# 2Rotary.net
KiCad netlist of a schematic drawn in EAGLE
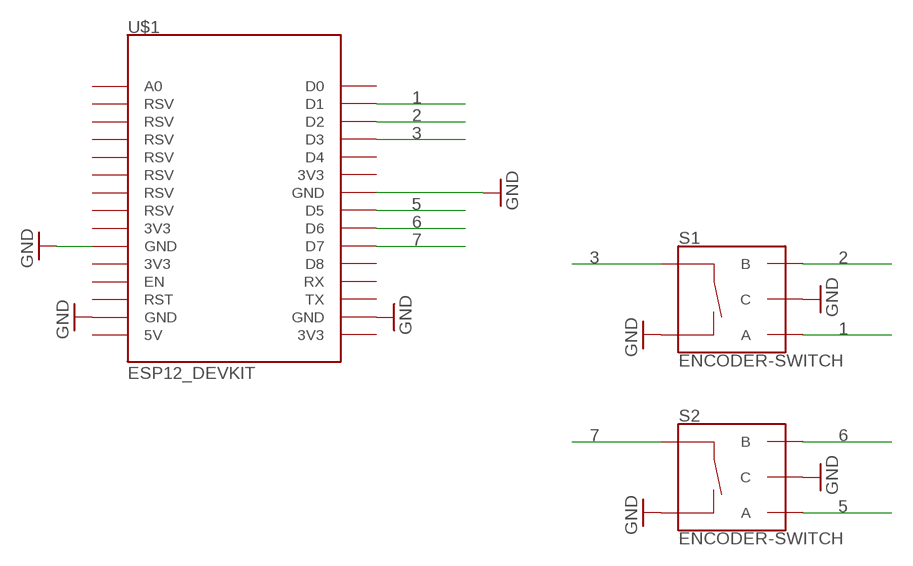
[diagram p0: schematic, sheet 1]

(export (version "E")
  (design (tool "Eeschema 10.0.6"))
  (components
    (comp (ref "S1")
      (value "ENCODER-SWITCH")
      (footprint "eagle-import:ROTARY_ENC_PLAIN")
      (libsource (lib "eagle-import") (part "ENCODER-SWITCH"))
    )
    (comp (ref "S2")
      (value "ENCODER-SWITCH")
      (footprint "eagle-import:ROTARY_ENC_PLAIN")
      (libsource (lib "eagle-import") (part "ENCODER-SWITCH"))
    )
    (comp (ref "U$1")
      (value "ESP12_DEVKIT")
      (footprint "eagle-import:ESP12_DEVKIT")
      (libsource (lib "eagle-import") (part "ESP12_DEVKIT"))
    )
  )
  (nets
    (net (code "1") (name "/1") (class "Default")
      (node (ref "S1") (pin "A") (pinfunction "A_A") (pintype "bidirectional"))
      (node (ref "U$1") (pin "D1") (pinfunction "D1_D1") (pintype "bidirectional"))
    )
    (net (code "2") (name "/2") (class "Default")
      (node (ref "S1") (pin "B") (pinfunction "B_B") (pintype "bidirectional"))
      (node (ref "U$1") (pin "D2") (pinfunction "D2_D2") (pintype "bidirectional"))
    )
    (net (code "3") (name "/3") (class "Default")
      (node (ref "S1") (pin "SW+") (pinfunction "SW+_SW+") (pintype "bidirectional"))
      (node (ref "U$1") (pin "D3") (pinfunction "D3_D3") (pintype "bidirectional"))
    )
    (net (code "4") (name "/5") (class "Default")
      (node (ref "S2") (pin "A") (pinfunction "A_A") (pintype "bidirectional"))
      (node (ref "U$1") (pin "D5") (pinfunction "D5_D5") (pintype "bidirectional"))
    )
    (net (code "5") (name "/6") (class "Default")
      (node (ref "S2") (pin "B") (pinfunction "B_B") (pintype "bidirectional"))
      (node (ref "U$1") (pin "D6") (pinfunction "D6_D6") (pintype "bidirectional"))
    )
    (net (code "6") (name "/7") (class "Default")
      (node (ref "S2") (pin "SW+") (pinfunction "SW+_SW+") (pintype "bidirectional"))
      (node (ref "U$1") (pin "D7") (pinfunction "D7_D7") (pintype "bidirectional"))
    )
    (net (code "7") (name "GND") (class "Default")
      (node (ref "S1") (pin "C") (pinfunction "C_C") (pintype "bidirectional"))
      (node (ref "S1") (pin "SW-") (pinfunction "SW-_SW-") (pintype "bidirectional"))
      (node (ref "S2") (pin "C") (pinfunction "C_C") (pintype "bidirectional"))
      (node (ref "S2") (pin "SW-") (pinfunction "SW-_SW-") (pintype "bidirectional"))
      (node (ref "U$1") (pin "GND@0") (pinfunction "GND_GND@0") (pintype "bidirectional"))
      (node (ref "U$1") (pin "GND@1") (pinfunction "GND_GND@1") (pintype "bidirectional"))
      (node (ref "U$1") (pin "GND@2") (pinfunction "GND_GND@2") (pintype "bidirectional"))
      (node (ref "U$1") (pin "GND@3") (pinfunction "GND_GND@3") (pintype "bidirectional"))
    )
    (net (code "8") (name "unconnected-(U$1-3V3-Pad3V3@0)") (class "Default")
      (node (ref "U$1") (pin "3V3@0") (pinfunction "3V3_3V3@0") (pintype "bidirectional"))
    )
    (net (code "9") (name "unconnected-(U$1-3V3-Pad3V3@1)") (class "Default")
      (node (ref "U$1") (pin "3V3@1") (pinfunction "3V3_3V3@1") (pintype "bidirectional"))
    )
    (net (code "10") (name "unconnected-(U$1-3V3-Pad3V3@2)") (class "Default")
      (node (ref "U$1") (pin "3V3@2") (pinfunction "3V3_3V3@2") (pintype "bidirectional"))
    )
    (net (code "11") (name "unconnected-(U$1-3V3-Pad3V3@3)") (class "Default")
      (node (ref "U$1") (pin "3V3@3") (pinfunction "3V3_3V3@3") (pintype "bidirectional"))
    )
    (net (code "12") (name "unconnected-(U$1-Pad5V)") (class "Default")
      (node (ref "U$1") (pin "5V") (pinfunction "5V_5V") (pintype "bidirectional"))
    )
    (net (code "13") (name "unconnected-(U$1-PadA0)") (class "Default")
      (node (ref "U$1") (pin "A0") (pinfunction "A0_A0") (pintype "bidirectional"))
    )
    (net (code "14") (name "unconnected-(U$1-PadD0)") (class "Default")
      (node (ref "U$1") (pin "D0") (pinfunction "D0_D0") (pintype "bidirectional"))
    )
    (net (code "15") (name "unconnected-(U$1-PadD4)") (class "Default")
      (node (ref "U$1") (pin "D4") (pinfunction "D4_D4") (pintype "bidirectional"))
    )
    (net (code "16") (name "unconnected-(U$1-PadD8)") (class "Default")
      (node (ref "U$1") (pin "D8") (pinfunction "D8_D8") (pintype "bidirectional"))
    )
    (net (code "17") (name "unconnected-(U$1-PadEN)") (class "Default")
      (node (ref "U$1") (pin "EN") (pinfunction "EN_EN") (pintype "bidirectional"))
    )
    (net (code "18") (name "unconnected-(U$1-PadRST)") (class "Default")
      (node (ref "U$1") (pin "RST") (pinfunction "RST_RST") (pintype "bidirectional"))
    )
    (net (code "19") (name "unconnected-(U$1-PadRX)") (class "Default")
      (node (ref "U$1") (pin "RX") (pinfunction "RX_RX") (pintype "bidirectional"))
    )
    (net (code "20") (name "unconnected-(U$1-PadTX)") (class "Default")
      (node (ref "U$1") (pin "TX") (pinfunction "TX_TX") (pintype "bidirectional"))
    )
    (net (code "21") (name "unconnected-(U$1-RSV-PadGND@4)") (class "Default")
      (node (ref "U$1") (pin "GND@4") (pinfunction "RSV_GND@4") (pintype "bidirectional"))
    )
    (net (code "22") (name "unconnected-(U$1-RSV-PadRSV@0)") (class "Default")
      (node (ref "U$1") (pin "RSV@0") (pinfunction "RSV_RSV@0") (pintype "bidirectional"))
    )
    (net (code "23") (name "unconnected-(U$1-RSV-PadRSV@1)") (class "Default")
      (node (ref "U$1") (pin "RSV@1") (pinfunction "RSV_RSV@1") (pintype "bidirectional"))
    )
    (net (code "24") (name "unconnected-(U$1-RSV-PadRSV@2)") (class "Default")
      (node (ref "U$1") (pin "RSV@2") (pinfunction "RSV_RSV@2") (pintype "bidirectional"))
    )
    (net (code "25") (name "unconnected-(U$1-RSV-PadRSV@3)") (class "Default")
      (node (ref "U$1") (pin "RSV@3") (pinfunction "RSV_RSV@3") (pintype "bidirectional"))
    )
    (net (code "26") (name "unconnected-(U$1-RSV-PadRSV@4)") (class "Default")
      (node (ref "U$1") (pin "RSV@4") (pinfunction "RSV_RSV@4") (pintype "bidirectional"))
    )
    (net (code "27") (name "unconnected-(U$1-RSV-PadRSV@5)") (class "Default")
      (node (ref "U$1") (pin "RSV@5") (pinfunction "RSV_RSV@5") (pintype "bidirectional"))
    )
  )
)
